# motor_board.net
KiCad netlist of a schematic drawn in EAGLE
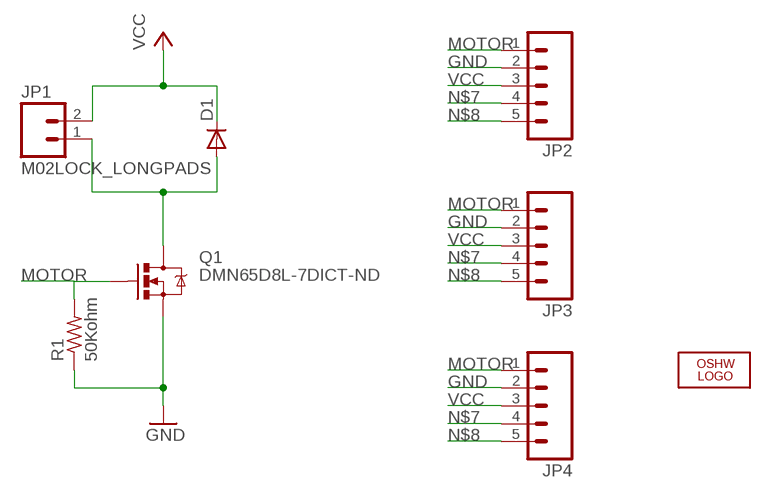
[diagram p0: schematic, sheet 1]

(export (version "E")
  (design (tool "Eeschema 10.0.6"))
  (components
    (comp (ref "D1")
      (value "DIODE-DO214AA")
      (footprint "eagle-import:DO214AA")
      (libsource (lib "eagle-import") (part "DIODE-DO214AA"))
    )
    (comp (ref "JP1")
      (value "M02LOCK_LONGPADS")
      (footprint "eagle-import:1X02_LOCK_LONGPADS")
      (libsource (lib "eagle-import") (part "M02LOCK_LONGPADS"))
    )
    (comp (ref "JP2")
      (value "M05PTH")
      (footprint "eagle-import:1X05")
      (libsource (lib "eagle-import") (part "M05PTH"))
    )
    (comp (ref "JP3")
      (value "M05PTH")
      (footprint "eagle-import:1X05")
      (libsource (lib "eagle-import") (part "M05PTH"))
    )
    (comp (ref "JP4")
      (value "M05PTH")
      (footprint "eagle-import:1X05")
      (libsource (lib "eagle-import") (part "M05PTH"))
    )
    (comp (ref "LOGO2")
      (value "OSHW_LOGO_6MILX0100-NT")
      (footprint "eagle-import:OSHW_6X100_NOTEXT")
      (libsource (lib "eagle-import") (part "OSHW_LOGO_6MILX0100-NT"))
    )
    (comp (ref "Q1")
      (value "DMN65D8L-7DICT-ND")
      (footprint "eagle-import:SOT23")
      (libsource (lib "eagle-import") (part "MOSFET-NCHANNELBSS138"))
    )
    (comp (ref "R1")
      (value "50Kohm")
      (footprint "eagle-import:M1206")
      (libsource (lib "eagle-import") (part "R-US_M1206"))
    )
  )
  (nets
    (net (code "1") (name "/MOTOR") (class "Default")
      (node (ref "JP2") (pin "1") (pinfunction "1_1") (pintype "passive"))
      (node (ref "JP3") (pin "1") (pinfunction "1_1") (pintype "passive"))
      (node (ref "JP4") (pin "1") (pinfunction "1_1") (pintype "passive"))
      (node (ref "Q1") (pin "1") (pinfunction "G_1") (pintype "passive"))
      (node (ref "R1") (pin "2") (pinfunction "2_2") (pintype "passive"))
    )
    (net (code "2") (name "/N$7") (class "Default")
      (node (ref "JP2") (pin "4") (pinfunction "4_4") (pintype "passive"))
      (node (ref "JP3") (pin "4") (pinfunction "4_4") (pintype "passive"))
      (node (ref "JP4") (pin "4") (pinfunction "4_4") (pintype "passive"))
    )
    (net (code "3") (name "/N$8") (class "Default")
      (node (ref "JP2") (pin "5") (pinfunction "5_5") (pintype "passive"))
      (node (ref "JP3") (pin "5") (pinfunction "5_5") (pintype "passive"))
      (node (ref "JP4") (pin "5") (pinfunction "5_5") (pintype "passive"))
    )
    (net (code "4") (name "GND") (class "Default")
      (node (ref "JP2") (pin "2") (pinfunction "2_2") (pintype "passive"))
      (node (ref "JP3") (pin "2") (pinfunction "2_2") (pintype "passive"))
      (node (ref "JP4") (pin "2") (pinfunction "2_2") (pintype "passive"))
      (node (ref "Q1") (pin "2") (pinfunction "S_2") (pintype "passive"))
      (node (ref "R1") (pin "1") (pinfunction "1_1") (pintype "passive"))
    )
    (net (code "5") (name "Net-(Q1-D)") (class "Default")
      (node (ref "D1") (pin "A") (pinfunction "A_A") (pintype "passive"))
      (node (ref "JP1") (pin "1") (pinfunction "1_1") (pintype "passive"))
      (node (ref "Q1") (pin "3") (pinfunction "D_3") (pintype "passive"))
    )
    (net (code "6") (name "VCC") (class "Default")
      (node (ref "D1") (pin "C") (pinfunction "C_C") (pintype "passive"))
      (node (ref "JP1") (pin "2") (pinfunction "2_2") (pintype "passive"))
      (node (ref "JP2") (pin "3") (pinfunction "3_3") (pintype "passive"))
      (node (ref "JP3") (pin "3") (pinfunction "3_3") (pintype "passive"))
      (node (ref "JP4") (pin "3") (pinfunction "3_3") (pintype "passive"))
    )
  )
)
